# Schematic_1.net
KiCad netlist of a schematic drawn in Altium Designer
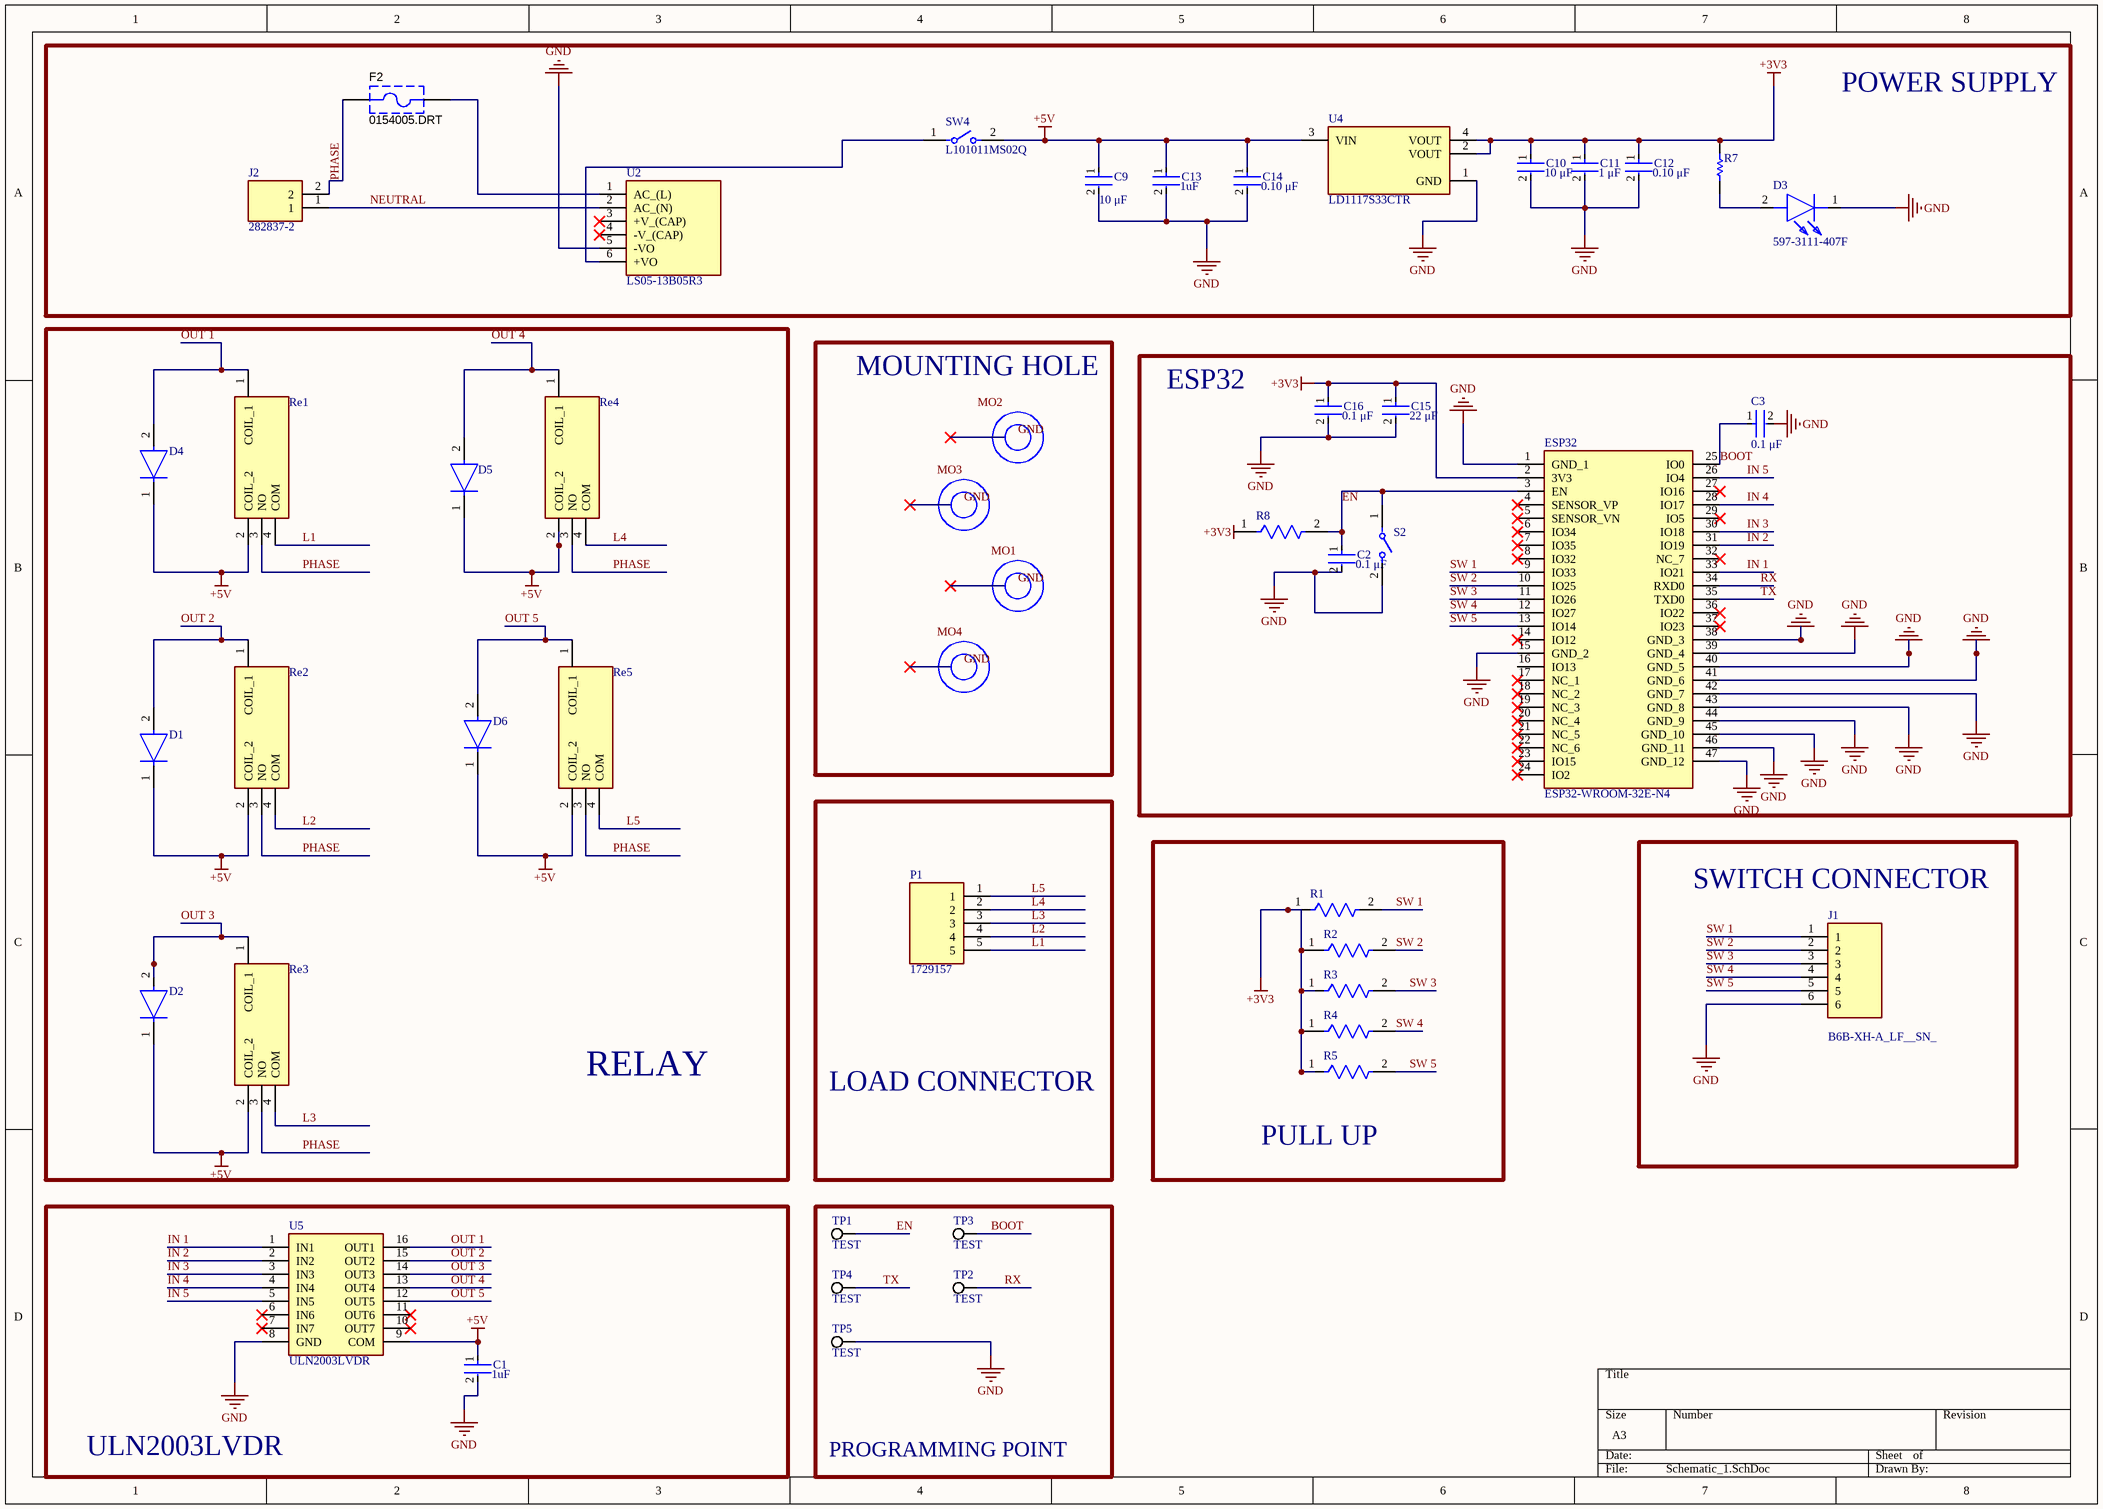
[diagram p0: Schematic_1.SchDoc]

(export (version "E")
  (design (tool "Eeschema 10.0.6"))
  (components
    (comp (ref "C1")
      (value "C0402C104K8PACTU")
      (footprint "FP-C0402-BB-MFG")
      (description "CAP CER 0.1UF 10V X5R 0402")
      (fields
        (field (name "CAPACITANCE") "1uF")
        (field (name "MANUFACTURER") "Kemet")
        (field (name "TOLERANCE") "0.1")
      )
      (libsource (lib "Altium Content Vault") (part "b4654b650e69147ec39a6b967a45e02"))
    )
    (comp (ref "C2")
      (value "0.1 μF")
      (footprint "FP-C0402-BB-MFG")
      (description "CAP CER 0.1UF 10V X5R 0402")
      (fields (field (name "MANUFACTURER") "Kemet") (field (name "TOLERANCE") "0.1"))
      (libsource (lib "Altium Content Vault") (part "b4654b650e69147ec39a6b967a45e02"))
    )
    (comp (ref "C3")
      (value "0.1 μF")
      (footprint "FP-C0402-BB-MFG")
      (description "CAP CER 0.1UF 10V X5R 0402")
      (fields (field (name "MANUFACTURER") "Kemet") (field (name "TOLERANCE") "0.1"))
      (libsource (lib "Altium Content Vault") (part "b4654b650e69147ec39a6b967a45e02"))
    )
    (comp (ref "C9")
      (value "10 μF")
      (footprint "FP-C0402-BB-MFG")
      (description "CAP CER 0.1UF 10V X5R 0402")
      (fields (field (name "MANUFACTURER") "Kemet") (field (name "TOLERANCE") "0.1"))
      (libsource (lib "Altium Content Vault") (part "b4654b650e69147ec39a6b967a45e02"))
    )
    (comp (ref "C10")
      (value "10 μF")
      (footprint "FP-C0402-BB-MFG")
      (description "CAP CER 0.1UF 10V X5R 0402")
      (fields (field (name "MANUFACTURER") "Kemet") (field (name "TOLERANCE") "0.1"))
      (libsource (lib "Altium Content Vault") (part "b4654b650e69147ec39a6b967a45e02"))
    )
    (comp (ref "C11")
      (value "1 μF")
      (footprint "FP-C0402-BB-MFG")
      (description "CAP CER 0.1UF 10V X5R 0402")
      (fields (field (name "MANUFACTURER") "Kemet") (field (name "TOLERANCE") "0.1"))
      (libsource (lib "Altium Content Vault") (part "b4654b650e69147ec39a6b967a45e02"))
    )
    (comp (ref "C12")
      (value "C0402C104K8PACTU")
      (footprint "FP-C0402-BB-MFG")
      (description "CAP CER 0.1UF 10V X5R 0402")
      (fields
        (field (name "CAPACITANCE") "0.10 μF")
        (field (name "MANUFACTURER") "Kemet")
        (field (name "TOLERANCE") "0.1")
      )
      (libsource (lib "Altium Content Vault") (part "b4654b650e69147ec39a6b967a45e02"))
    )
    (comp (ref "C13")
      (value "C0402C104K8PACTU")
      (footprint "FP-C0402-BB-MFG")
      (description "CAP CER 0.1UF 10V X5R 0402")
      (fields
        (field (name "CAPACITANCE") "1uF")
        (field (name "MANUFACTURER") "Kemet")
        (field (name "TOLERANCE") "0.1")
      )
      (libsource (lib "Altium Content Vault") (part "b4654b650e69147ec39a6b967a45e02"))
    )
    (comp (ref "C14")
      (value "0.10 μF")
      (footprint "FP-C0402-BB-MFG")
      (description "CAP CER 0.1UF 10V X5R 0402")
      (fields (field (name "MANUFACTURER") "Kemet") (field (name "TOLERANCE") "0.1"))
      (libsource (lib "Altium Content Vault") (part "b4654b650e69147ec39a6b967a45e02"))
    )
    (comp (ref "C15")
      (value "22 μF")
      (footprint "FP-C0402-BB-MFG")
      (description "CAP CER 0.1UF 10V X5R 0402")
      (fields (field (name "MANUFACTURER") "Kemet") (field (name "TOLERANCE") "0.1"))
      (libsource (lib "Altium Content Vault") (part "b4654b650e69147ec39a6b967a45e02"))
    )
    (comp (ref "C16")
      (value "0.1 μF")
      (footprint "FP-C0402-BB-MFG")
      (description "CAP CER 0.1UF 10V X5R 0402")
      (fields (field (name "MANUFACTURER") "Kemet") (field (name "TOLERANCE") "0.1"))
      (libsource (lib "Altium Content Vault") (part "b4654b650e69147ec39a6b967a45e02"))
    )
    (comp (ref "D1")
      (value "1N4148")
      (footprint "FP-017AG-MFG")
      (description "DIODE GEN PURP 100V 200MA DO35")
      (fields (field (name "VOLTAGE") "100V"))
      (libsource (lib "Altium Content Vault") (part "d7152d700b627762746794eb795d46e"))
    )
    (comp (ref "D2")
      (value "1N4148")
      (footprint "FP-017AG-MFG")
      (description "DIODE GEN PURP 100V 200MA DO35")
      (fields (field (name "VOLTAGE") "100V"))
      (libsource (lib "Altium Content Vault") (part "d7152d700b627762746794eb795d46e"))
    )
    (comp (ref "D3")
      (value "597-3111-407F")
      (footprint "SamacSys:LEDC3015X150N")
      (description "LED")
      (fields (field (name "MOUSER PART NUMBER") "645-597-3111-407F"))
      (libsource (lib "*") (part "597-3111-407F"))
    )
    (comp (ref "D4")
      (value "1N4148")
      (footprint "FP-017AG-MFG")
      (description "DIODE GEN PURP 100V 200MA DO35")
      (fields (field (name "VOLTAGE") "100V"))
      (libsource (lib "Altium Content Vault") (part "d7152d700b627762746794eb795d46e"))
    )
    (comp (ref "D5")
      (value "1N4148")
      (footprint "FP-017AG-MFG")
      (description "DIODE GEN PURP 100V 200MA DO35")
      (fields (field (name "VOLTAGE") "100V"))
      (libsource (lib "Altium Content Vault") (part "d7152d700b627762746794eb795d46e"))
    )
    (comp (ref "D6")
      (value "1N4148")
      (footprint "FP-017AG-MFG")
      (description "DIODE GEN PURP 100V 200MA DO35")
      (fields (field (name "VOLTAGE") "100V"))
      (libsource (lib "Altium Content Vault") (part "d7152d700b627762746794eb795d46e"))
    )
    (comp (ref "ESP32")
      (value "ESP32-WROOM-32E-N4")
      (footprint "SamacSys:ESP32WROOM32EN4")
      (description "Integrated Circuit")
      (fields (field (name "MOUSER PART NUMBER") "356-ESP32WRM32E132PH"))
      (libsource (lib "*") (part "ESP32-WROOM-32E-N4"))
    )
    (comp (ref "F2")
      (value "0154005.DRT")
      (footprint "LFUS-154_V")
      (description "Fuse and Holder Combination, 125 V, 5 A, -55 to 125 degC, 2-Pin SMD, RoHS, Tape and Reel")
      (fields (field (name "MANUFACTURER") "Littelfuse"))
      (libsource (lib "Altium Content Vault") (part "FUSE_HOLDER-2"))
    )
    (comp (ref "J1")
      (value "B6B-XH-A_LF__SN_")
      (footprint "SamacSys:SHDR6W64P0X250_1X6_1740X575X700P")
      (description "Connector")
      (fields
        (field (name "MANUFACTURER_PART_NUMBER") "B6B-XH-A(LF)(SN)")
        (field (name "MOUSER PART NUMBER") "306-B6BXHALFSN")
      )
      (libsource (lib "*") (part "B6B-XH-A_LF__SN_"))
    )
    (comp (ref "J2")
      (value "282837-2")
      (footprint "SamacSys:2828372")
      (description "Connector")
      (fields (field (name "MOUSER PART NUMBER") "571-2828372"))
      (libsource (lib "*") (part "282837-2"))
    )
    (comp (ref "P1")
      (value "1729157")
      (footprint "SamacSys:1729157")
      (description "Connector")
      (fields (field (name "MOUSER PART NUMBER") "651-1729157"))
      (libsource (lib "*") (part "1729157"))
    )
    (comp (ref "R1")
      (value "CRCW040210K0JNED")
      (footprint "FP-CRCW0402-e3-IPC_B")
      (description "RES Thick Film, 10kΩ, 5%, 0.063W, 200ppm/°C, 0402")
      (fields (field (name "TOLERANCE") "5%"))
      (libsource (lib "Altium Content Vault") (part "1029c3af85768c4190bb7ad29bc67b5"))
    )
    (comp (ref "R2")
      (value "CRCW040210K0JNED")
      (footprint "FP-CRCW0402-e3-IPC_B")
      (description "RES Thick Film, 10kΩ, 5%, 0.063W, 200ppm/°C, 0402")
      (fields (field (name "TOLERANCE") "5%"))
      (libsource (lib "Altium Content Vault") (part "1029c3af85768c4190bb7ad29bc67b5"))
    )
    (comp (ref "R3")
      (value "CRCW040210K0JNED")
      (footprint "FP-CRCW0402-e3-IPC_B")
      (description "RES Thick Film, 10kΩ, 5%, 0.063W, 200ppm/°C, 0402")
      (fields (field (name "TOLERANCE") "5%"))
      (libsource (lib "Altium Content Vault") (part "1029c3af85768c4190bb7ad29bc67b5"))
    )
    (comp (ref "R4")
      (value "CRCW040210K0JNED")
      (footprint "FP-CRCW0402-e3-IPC_B")
      (description "RES Thick Film, 10kΩ, 5%, 0.063W, 200ppm/°C, 0402")
      (fields (field (name "TOLERANCE") "5%"))
      (libsource (lib "Altium Content Vault") (part "1029c3af85768c4190bb7ad29bc67b5"))
    )
    (comp (ref "R5")
      (value "CRCW040210K0JNED")
      (footprint "FP-CRCW0402-e3-IPC_B")
      (description "RES Thick Film, 10kΩ, 5%, 0.063W, 200ppm/°C, 0402")
      (fields (field (name "TOLERANCE") "5%"))
      (libsource (lib "Altium Content Vault") (part "1029c3af85768c4190bb7ad29bc67b5"))
    )
    (comp (ref "R7")
      (value "ERJ-3EKF3300V")
      (footprint "RESC1608X55X30LL15T15")
      (description "Chip Resistor, 330 Ohm, +/- 1%, 0.1 W, -55 to 155 degC, 0603 (1608 Metric), RoHS, Tape and Reel")
      (libsource (lib "Altium Content Vault") (part "RES-2"))
    )
    (comp (ref "R8")
      (value "CRCW040210K0JNED")
      (footprint "FP-CRCW0402-e3-IPC_B")
      (description "RES Thick Film, 10kΩ, 5%, 0.063W, 200ppm/°C, 0402")
      (fields (field (name "TOLERANCE") "5%"))
      (libsource (lib "Altium Content Vault") (part "1029c3af85768c4190bb7ad29bc67b5"))
    )
    (comp (ref "Re1")
      (value "HF46F-G_5-HS1T")
      (footprint "SamacSys:HF46FG5HS1T")
      (description "Relay or Contactor")
      (fields (field (name "MANUFACTURER_PART_NUMBER") "HF46F-G/5-HS1T"))
      (libsource (lib "*") (part "HF46F-G_5-HS1T"))
    )
    (comp (ref "Re2")
      (value "HF46F-G_5-HS1T")
      (footprint "SamacSys:HF46FG5HS1T")
      (description "Relay or Contactor")
      (fields (field (name "MANUFACTURER_PART_NUMBER") "HF46F-G/5-HS1T"))
      (libsource (lib "*") (part "HF46F-G_5-HS1T"))
    )
    (comp (ref "Re3")
      (value "HF46F-G_5-HS1T")
      (footprint "SamacSys:HF46FG5HS1T")
      (description "Relay or Contactor")
      (fields (field (name "MANUFACTURER_PART_NUMBER") "HF46F-G/5-HS1T"))
      (libsource (lib "*") (part "HF46F-G_5-HS1T"))
    )
    (comp (ref "Re4")
      (value "HF46F-G_5-HS1T")
      (footprint "SamacSys:HF46FG5HS1T")
      (description "Relay or Contactor")
      (fields (field (name "MANUFACTURER_PART_NUMBER") "HF46F-G/5-HS1T"))
      (libsource (lib "*") (part "HF46F-G_5-HS1T"))
    )
    (comp (ref "Re5")
      (value "HF46F-G_5-HS1T")
      (footprint "SamacSys:HF46FG5HS1T")
      (description "Relay or Contactor")
      (fields (field (name "MANUFACTURER_PART_NUMBER") "HF46F-G/5-HS1T"))
      (libsource (lib "*") (part "HF46F-G_5-HS1T"))
    )
    (comp (ref "S2")
      (value "L101011MS02Q")
      (footprint "FP-L101011MS02Q-MFG")
      (description "SWITCH SLIDE SPST 4A 125V")
      (libsource (lib "Altium Content Vault") (part "bb27bde45df87f1f469753f287ef5ae"))
    )
    (comp (ref "SW4")
      (value "L101011MS02Q")
      (footprint "FP-L101011MS02Q-MFG")
      (description "SWITCH SLIDE SPST 4A 125V")
      (libsource (lib "Altium Content Vault") (part "bb27bde45df87f1f469753f287ef5ae"))
    )
    (comp (ref "TP1")
      (value "TEST")
      (footprint "KSTN-5012_V")
      (description "Test Point, White, Through Hole, RoHS, Bulk")
      (fields (field (name "MANUFACTURER") "Keystone"))
      (libsource (lib "Altium Content Vault") (part "TESTPOINT_WHITE"))
    )
    (comp (ref "TP2")
      (value "TEST")
      (footprint "KSTN-5012_V")
      (description "Test Point, White, Through Hole, RoHS, Bulk")
      (fields (field (name "MANUFACTURER") "Keystone"))
      (libsource (lib "Altium Content Vault") (part "TESTPOINT_WHITE"))
    )
    (comp (ref "TP3")
      (value "TEST")
      (footprint "KSTN-5012_V")
      (description "Test Point, White, Through Hole, RoHS, Bulk")
      (fields (field (name "MANUFACTURER") "Keystone"))
      (libsource (lib "Altium Content Vault") (part "TESTPOINT_WHITE"))
    )
    (comp (ref "TP4")
      (value "TEST")
      (footprint "KSTN-5012_V")
      (description "Test Point, White, Through Hole, RoHS, Bulk")
      (fields (field (name "MANUFACTURER") "Keystone"))
      (libsource (lib "Altium Content Vault") (part "TESTPOINT_WHITE"))
    )
    (comp (ref "TP5")
      (value "TEST")
      (footprint "KSTN-5012_V")
      (description "Test Point, White, Through Hole, RoHS, Bulk")
      (fields (field (name "MANUFACTURER") "Keystone"))
      (libsource (lib "Altium Content Vault") (part "TESTPOINT_WHITE"))
    )
    (comp (ref "U2")
      (value "LS05-13B05R3")
      (footprint "SamacSys:LS0513B05R3")
      (description "Power Supply")
      (libsource (lib "*") (part "LS05-13B05R3"))
    )
    (comp (ref "U4")
      (value "LD1117S33CTR")
      (footprint "FP-SOT-223-0046067_14-MFG")
      (description "IC REG LINEAR 3.3V 800MA SOT223")
      (libsource (lib "Altium Content Vault") (part "7818869c5c16ceab15634627166a29d"))
    )
    (comp (ref "U5")
      (value "ULN2003LVDR")
      (footprint "SamacSys:SOIC127P600X175-16N")
      (description "Integrated Circuit")
      (fields (field (name "MOUSER PART NUMBER") "595-ULN2003LVDR"))
      (libsource (lib "*") (part "ULN2003LVDR"))
    )
  )
  (nets
    (net (code "1") (name "+3V3") (class "Default")
      (node (ref "C10") (pin "1") (pinfunction "1_1") (pintype "passive"))
      (node (ref "C11") (pin "1") (pinfunction "1_1") (pintype "passive"))
      (node (ref "C12") (pin "1") (pinfunction "1_1") (pintype "passive"))
      (node (ref "C15") (pin "1") (pinfunction "1_1") (pintype "passive"))
      (node (ref "C16") (pin "1") (pinfunction "1_1") (pintype "passive"))
      (node (ref "ESP32") (pin "2") (pinfunction "3V3_2") (pintype "passive"))
      (node (ref "R1") (pin "1") (pinfunction "1_1") (pintype "passive"))
      (node (ref "R2") (pin "1") (pinfunction "1_1") (pintype "passive"))
      (node (ref "R3") (pin "1") (pinfunction "1_1") (pintype "passive"))
      (node (ref "R4") (pin "1") (pinfunction "1_1") (pintype "passive"))
      (node (ref "R5") (pin "1") (pinfunction "1_1") (pintype "passive"))
      (node (ref "R7") (pin "2") (pinfunction "2_2") (pintype "passive"))
      (node (ref "U4") (pin "2") (pinfunction "VOUT_2") (pintype "power_in"))
      (node (ref "U4") (pin "4") (pinfunction "VOUT_4") (pintype "power_in"))
    )
    (net (code "2") (name "+5V") (class "Default")
      (node (ref "C1") (pin "1") (pinfunction "1_1") (pintype "passive"))
      (node (ref "C13") (pin "1") (pinfunction "1_1") (pintype "passive"))
      (node (ref "C14") (pin "1") (pinfunction "1_1") (pintype "passive"))
      (node (ref "C9") (pin "1") (pinfunction "1_1") (pintype "passive"))
      (node (ref "D1") (pin "1") (pinfunction "C_1") (pintype "passive"))
      (node (ref "D2") (pin "1") (pinfunction "C_1") (pintype "passive"))
      (node (ref "D4") (pin "1") (pinfunction "C_1") (pintype "passive"))
      (node (ref "D5") (pin "1") (pinfunction "C_1") (pintype "passive"))
      (node (ref "D6") (pin "1") (pinfunction "C_1") (pintype "passive"))
      (node (ref "Re1") (pin "2") (pinfunction "COIL_2_2") (pintype "passive"))
      (node (ref "Re2") (pin "2") (pinfunction "COIL_2_2") (pintype "passive"))
      (node (ref "Re3") (pin "2") (pinfunction "COIL_2_2") (pintype "passive"))
      (node (ref "Re4") (pin "2") (pinfunction "COIL_2_2") (pintype "passive"))
      (node (ref "Re5") (pin "2") (pinfunction "COIL_2_2") (pintype "passive"))
      (node (ref "SW4") (pin "2") (pinfunction "2_2") (pintype "passive"))
      (node (ref "U4") (pin "3") (pinfunction "VIN_3") (pintype "power_in"))
      (node (ref "U5") (pin "9") (pinfunction "COM_9") (pintype "passive"))
    )
    (net (code "3") (name "/BOOT") (class "Default")
      (node (ref "C3") (pin "1") (pinfunction "1_1") (pintype "passive"))
      (node (ref "ESP32") (pin "25") (pinfunction "IO0_25") (pintype "passive"))
      (node (ref "TP3") (pin "1") (pinfunction "1_1") (pintype "passive"))
    )
    (net (code "4") (name "/EN") (class "Default")
      (node (ref "C2") (pin "1") (pinfunction "1_1") (pintype "passive"))
      (node (ref "ESP32") (pin "3") (pinfunction "EN_3") (pintype "passive"))
      (node (ref "R8") (pin "2") (pinfunction "2_2") (pintype "passive"))
      (node (ref "S2") (pin "1") (pinfunction "1_1") (pintype "passive"))
      (node (ref "TP1") (pin "1") (pinfunction "1_1") (pintype "passive"))
    )
    (net (code "5") (name "/IN 1") (class "Default")
      (node (ref "ESP32") (pin "33") (pinfunction "IO21_33") (pintype "passive"))
      (node (ref "U5") (pin "1") (pinfunction "IN1_1") (pintype "passive"))
    )
    (net (code "6") (name "/IN 2") (class "Default")
      (node (ref "ESP32") (pin "31") (pinfunction "IO19_31") (pintype "passive"))
      (node (ref "U5") (pin "2") (pinfunction "IN2_2") (pintype "passive"))
    )
    (net (code "7") (name "/IN 3") (class "Default")
      (node (ref "ESP32") (pin "30") (pinfunction "IO18_30") (pintype "passive"))
      (node (ref "U5") (pin "3") (pinfunction "IN3_3") (pintype "passive"))
    )
    (net (code "8") (name "/IN 4") (class "Default")
      (node (ref "ESP32") (pin "28") (pinfunction "IO17_28") (pintype "passive"))
      (node (ref "U5") (pin "4") (pinfunction "IN4_4") (pintype "passive"))
    )
    (net (code "9") (name "/IN 5") (class "Default")
      (node (ref "ESP32") (pin "26") (pinfunction "IO4_26") (pintype "passive"))
      (node (ref "U5") (pin "5") (pinfunction "IN5_5") (pintype "passive"))
    )
    (net (code "10") (name "/L1") (class "Default")
      (node (ref "P1") (pin "5") (pinfunction "5_5") (pintype "passive"))
      (node (ref "Re1") (pin "4") (pinfunction "COM_4") (pintype "passive"))
    )
    (net (code "11") (name "/L2") (class "Default")
      (node (ref "P1") (pin "4") (pinfunction "4_4") (pintype "passive"))
      (node (ref "Re2") (pin "4") (pinfunction "COM_4") (pintype "passive"))
    )
    (net (code "12") (name "/L3") (class "Default")
      (node (ref "P1") (pin "3") (pinfunction "3_3") (pintype "passive"))
      (node (ref "Re3") (pin "4") (pinfunction "COM_4") (pintype "passive"))
    )
    (net (code "13") (name "/L4") (class "Default")
      (node (ref "P1") (pin "2") (pinfunction "2_2") (pintype "passive"))
      (node (ref "Re4") (pin "4") (pinfunction "COM_4") (pintype "passive"))
    )
    (net (code "14") (name "/L5") (class "Default")
      (node (ref "P1") (pin "1") (pinfunction "1_1") (pintype "passive"))
      (node (ref "Re5") (pin "4") (pinfunction "COM_4") (pintype "passive"))
    )
    (net (code "19") (name "/NEUTRAL") (class "Default")
      (node (ref "J2") (pin "1") (pinfunction "1_1") (pintype "passive"))
      (node (ref "U2") (pin "2") (pinfunction "AC_(N)_2") (pintype "passive"))
    )
    (net (code "20") (name "/OUT 1") (class "Default")
      (node (ref "D4") (pin "2") (pinfunction "A_2") (pintype "passive"))
      (node (ref "Re1") (pin "1") (pinfunction "COIL_1_1") (pintype "passive"))
      (node (ref "U5") (pin "16") (pinfunction "OUT1_16") (pintype "passive"))
    )
    (net (code "21") (name "/OUT 2") (class "Default")
      (node (ref "D1") (pin "2") (pinfunction "A_2") (pintype "passive"))
      (node (ref "Re2") (pin "1") (pinfunction "COIL_1_1") (pintype "passive"))
      (node (ref "U5") (pin "15") (pinfunction "OUT2_15") (pintype "passive"))
    )
    (net (code "22") (name "/OUT 3") (class "Default")
      (node (ref "D2") (pin "2") (pinfunction "A_2") (pintype "passive"))
      (node (ref "Re3") (pin "1") (pinfunction "COIL_1_1") (pintype "passive"))
      (node (ref "U5") (pin "14") (pinfunction "OUT3_14") (pintype "passive"))
    )
    (net (code "23") (name "/OUT 4") (class "Default")
      (node (ref "D5") (pin "2") (pinfunction "A_2") (pintype "passive"))
      (node (ref "Re4") (pin "1") (pinfunction "COIL_1_1") (pintype "passive"))
      (node (ref "U5") (pin "13") (pinfunction "OUT4_13") (pintype "passive"))
    )
    (net (code "24") (name "/OUT 5") (class "Default")
      (node (ref "D6") (pin "2") (pinfunction "A_2") (pintype "passive"))
      (node (ref "Re5") (pin "1") (pinfunction "COIL_1_1") (pintype "passive"))
      (node (ref "U5") (pin "12") (pinfunction "OUT5_12") (pintype "passive"))
    )
    (net (code "25") (name "/PHASE") (class "Default")
      (node (ref "F2") (pin "1") (pinfunction "1_1") (pintype "passive"))
      (node (ref "J2") (pin "2") (pinfunction "2_2") (pintype "passive"))
      (node (ref "Re1") (pin "3") (pinfunction "NO_3") (pintype "passive"))
      (node (ref "Re2") (pin "3") (pinfunction "NO_3") (pintype "passive"))
      (node (ref "Re3") (pin "3") (pinfunction "NO_3") (pintype "passive"))
      (node (ref "Re4") (pin "3") (pinfunction "NO_3") (pintype "passive"))
      (node (ref "Re5") (pin "3") (pinfunction "NO_3") (pintype "passive"))
    )
    (net (code "26") (name "/RX") (class "Default")
      (node (ref "ESP32") (pin "34") (pinfunction "RXD0_34") (pintype "passive"))
      (node (ref "TP2") (pin "1") (pinfunction "1_1") (pintype "passive"))
    )
    (net (code "27") (name "/SW 1") (class "Default")
      (node (ref "ESP32") (pin "9") (pinfunction "IO33_9") (pintype "passive"))
      (node (ref "J1") (pin "1") (pinfunction "1_1") (pintype "passive"))
      (node (ref "R1") (pin "2") (pinfunction "2_2") (pintype "passive"))
    )
    (net (code "28") (name "/SW 2") (class "Default")
      (node (ref "ESP32") (pin "10") (pinfunction "IO25_10") (pintype "passive"))
      (node (ref "J1") (pin "2") (pinfunction "2_2") (pintype "passive"))
      (node (ref "R2") (pin "2") (pinfunction "2_2") (pintype "passive"))
    )
    (net (code "29") (name "/SW 3") (class "Default")
      (node (ref "ESP32") (pin "11") (pinfunction "IO26_11") (pintype "passive"))
      (node (ref "J1") (pin "3") (pinfunction "3_3") (pintype "passive"))
      (node (ref "R3") (pin "2") (pinfunction "2_2") (pintype "passive"))
    )
    (net (code "30") (name "/SW 4") (class "Default")
      (node (ref "ESP32") (pin "12") (pinfunction "IO27_12") (pintype "passive"))
      (node (ref "J1") (pin "4") (pinfunction "4_4") (pintype "passive"))
      (node (ref "R4") (pin "2") (pinfunction "2_2") (pintype "passive"))
    )
    (net (code "31") (name "/SW 5") (class "Default")
      (node (ref "ESP32") (pin "13") (pinfunction "IO14_13") (pintype "passive"))
      (node (ref "J1") (pin "5") (pinfunction "5_5") (pintype "passive"))
      (node (ref "R5") (pin "2") (pinfunction "2_2") (pintype "passive"))
    )
    (net (code "32") (name "/TX") (class "Default")
      (node (ref "ESP32") (pin "35") (pinfunction "TXD0_35") (pintype "passive"))
      (node (ref "TP4") (pin "1") (pinfunction "1_1") (pintype "passive"))
    )
    (net (code "33") (name "GND") (class "Default")
      (node (ref "C1") (pin "2") (pinfunction "2_2") (pintype "passive"))
      (node (ref "C10") (pin "2") (pinfunction "2_2") (pintype "passive"))
      (node (ref "C11") (pin "2") (pinfunction "2_2") (pintype "passive"))
      (node (ref "C12") (pin "2") (pinfunction "2_2") (pintype "passive"))
      (node (ref "C13") (pin "2") (pinfunction "2_2") (pintype "passive"))
      (node (ref "C14") (pin "2") (pinfunction "2_2") (pintype "passive"))
      (node (ref "C15") (pin "2") (pinfunction "2_2") (pintype "passive"))
      (node (ref "C16") (pin "2") (pinfunction "2_2") (pintype "passive"))
      (node (ref "C2") (pin "2") (pinfunction "2_2") (pintype "passive"))
      (node (ref "C3") (pin "2") (pinfunction "2_2") (pintype "passive"))
      (node (ref "C9") (pin "2") (pinfunction "2_2") (pintype "passive"))
      (node (ref "D3") (pin "1") (pinfunction "K_1") (pintype "passive"))
      (node (ref "ESP32") (pin "1") (pinfunction "GND_1_1") (pintype "passive"))
      (node (ref "ESP32") (pin "15") (pinfunction "GND_2_15") (pintype "passive"))
      (node (ref "ESP32") (pin "38") (pinfunction "GND_3_38") (pintype "passive"))
      (node (ref "ESP32") (pin "39") (pinfunction "GND_4_39") (pintype "passive"))
      (node (ref "ESP32") (pin "40") (pinfunction "GND_5_40") (pintype "passive"))
      (node (ref "ESP32") (pin "41") (pinfunction "GND_6_41") (pintype "passive"))
      (node (ref "ESP32") (pin "42") (pinfunction "GND_7_42") (pintype "passive"))
      (node (ref "ESP32") (pin "43") (pinfunction "GND_8_43") (pintype "passive"))
      (node (ref "ESP32") (pin "44") (pinfunction "GND_9_44") (pintype "passive"))
      (node (ref "ESP32") (pin "45") (pinfunction "GND_10_45") (pintype "passive"))
      (node (ref "ESP32") (pin "46") (pinfunction "GND_11_46") (pintype "passive"))
      (node (ref "ESP32") (pin "47") (pinfunction "GND_12_47") (pintype "passive"))
      (node (ref "J1") (pin "6") (pinfunction "6_6") (pintype "passive"))
      (node (ref "S2") (pin "2") (pinfunction "2_2") (pintype "passive"))
      (node (ref "TP5") (pin "1") (pinfunction "1_1") (pintype "passive"))
      (node (ref "U2") (pin "5") (pinfunction "-VO_5") (pintype "passive"))
      (node (ref "U4") (pin "1") (pinfunction "GND_1") (pintype "power_in"))
      (node (ref "U5") (pin "8") (pinfunction "GND_8") (pintype "passive"))
    )
    (net (code "34") (name "Net-(D3-A)") (class "Default")
      (node (ref "D3") (pin "2") (pinfunction "A_2") (pintype "passive"))
      (node (ref "R7") (pin "1") (pinfunction "1_1") (pintype "passive"))
    )
    (net (code "35") (name "Net-(U2-+VO)") (class "Default")
      (node (ref "SW4") (pin "1") (pinfunction "1_1") (pintype "passive"))
      (node (ref "U2") (pin "6") (pinfunction "+VO_6") (pintype "passive"))
    )
    (net (code "36") (name "Net-(U2-AC_(L))") (class "Default")
      (node (ref "F2") (pin "2") (pinfunction "2_2") (pintype "passive"))
      (node (ref "U2") (pin "1") (pinfunction "AC_(L)_1") (pintype "passive"))
    )
    (net (code "37") (name "unconnected-(ESP32-IO2-Pad24)") (class "Default")
      (node (ref "ESP32") (pin "24") (pinfunction "IO2_24") (pintype "passive+no_connect"))
    )
    (net (code "38") (name "unconnected-(ESP32-IO5-Pad29)") (class "Default")
      (node (ref "ESP32") (pin "29") (pinfunction "IO5_29") (pintype "passive+no_connect"))
    )
    (net (code "39") (name "unconnected-(ESP32-IO12-Pad14)") (class "Default")
      (node (ref "ESP32") (pin "14") (pinfunction "IO12_14") (pintype "passive+no_connect"))
    )
    (net (code "40") (name "unconnected-(ESP32-IO13-Pad16)") (class "Default")
      (node (ref "ESP32") (pin "16") (pinfunction "IO13_16") (pintype "passive"))
    )
    (net (code "41") (name "unconnected-(ESP32-IO15-Pad23)") (class "Default")
      (node (ref "ESP32") (pin "23") (pinfunction "IO15_23") (pintype "passive+no_connect"))
    )
    (net (code "42") (name "unconnected-(ESP32-IO16-Pad27)") (class "Default")
      (node (ref "ESP32") (pin "27") (pinfunction "IO16_27") (pintype "passive+no_connect"))
    )
    (net (code "43") (name "unconnected-(ESP32-IO22-Pad36)") (class "Default")
      (node (ref "ESP32") (pin "36") (pinfunction "IO22_36") (pintype "passive+no_connect"))
    )
    (net (code "44") (name "unconnected-(ESP32-IO23-Pad37)") (class "Default")
      (node (ref "ESP32") (pin "37") (pinfunction "IO23_37") (pintype "passive+no_connect"))
    )
    (net (code "45") (name "unconnected-(ESP32-IO32-Pad8)") (class "Default")
      (node (ref "ESP32") (pin "8") (pinfunction "IO32_8") (pintype "passive+no_connect"))
    )
    (net (code "46") (name "unconnected-(ESP32-IO34-Pad6)") (class "Default")
      (node (ref "ESP32") (pin "6") (pinfunction "IO34_6") (pintype "passive+no_connect"))
    )
    (net (code "47") (name "unconnected-(ESP32-IO35-Pad7)") (class "Default")
      (node (ref "ESP32") (pin "7") (pinfunction "IO35_7") (pintype "passive+no_connect"))
    )
    (net (code "48") (name "unconnected-(ESP32-NC_1-Pad17)") (class "Default")
      (node (ref "ESP32") (pin "17") (pinfunction "NC_1_17") (pintype "passive+no_connect"))
    )
    (net (code "49") (name "unconnected-(ESP32-NC_2-Pad18)") (class "Default")
      (node (ref "ESP32") (pin "18") (pinfunction "NC_2_18") (pintype "passive+no_connect"))
    )
    (net (code "50") (name "unconnected-(ESP32-NC_3-Pad19)") (class "Default")
      (node (ref "ESP32") (pin "19") (pinfunction "NC_3_19") (pintype "passive+no_connect"))
    )
    (net (code "51") (name "unconnected-(ESP32-NC_4-Pad20)") (class "Default")
      (node (ref "ESP32") (pin "20") (pinfunction "NC_4_20") (pintype "passive+no_connect"))
    )
    (net (code "52") (name "unconnected-(ESP32-NC_5-Pad21)") (class "Default")
      (node (ref "ESP32") (pin "21") (pinfunction "NC_5_21") (pintype "passive+no_connect"))
    )
    (net (code "53") (name "unconnected-(ESP32-NC_6-Pad22)") (class "Default")
      (node (ref "ESP32") (pin "22") (pinfunction "NC_6_22") (pintype "passive+no_connect"))
    )
    (net (code "54") (name "unconnected-(ESP32-NC_7-Pad32)") (class "Default")
      (node (ref "ESP32") (pin "32") (pinfunction "NC_7_32") (pintype "passive+no_connect"))
    )
    (net (code "55") (name "unconnected-(ESP32-SENSOR_VN-Pad5)") (class "Default")
      (node (ref "ESP32") (pin "5") (pinfunction "SENSOR_VN_5") (pintype "passive+no_connect"))
    )
    (net (code "56") (name "unconnected-(ESP32-SENSOR_VP-Pad4)") (class "Default")
      (node (ref "ESP32") (pin "4") (pinfunction "SENSOR_VP_4") (pintype "passive+no_connect"))
    )
    (net (code "57") (name "unconnected-(R8-Pad1)") (class "Default")
      (node (ref "R8") (pin "1") (pinfunction "1_1") (pintype "passive"))
    )
    (net (code "58") (name "unconnected-(U2-+V_(CAP)-Pad3)") (class "Default")
      (node (ref "U2") (pin "3") (pinfunction "+V_(CAP)_3") (pintype "passive+no_connect"))
    )
    (net (code "59") (name "unconnected-(U2--V_(CAP)-Pad4)") (class "Default")
      (node (ref "U2") (pin "4") (pinfunction "-V_(CAP)_4") (pintype "passive+no_connect"))
    )
    (net (code "60") (name "unconnected-(U5-IN6-Pad6)") (class "Default")
      (node (ref "U5") (pin "6") (pinfunction "IN6_6") (pintype "passive+no_connect"))
    )
    (net (code "61") (name "unconnected-(U5-IN7-Pad7)") (class "Default")
      (node (ref "U5") (pin "7") (pinfunction "IN7_7") (pintype "passive+no_connect"))
    )
    (net (code "62") (name "unconnected-(U5-OUT6-Pad11)") (class "Default")
      (node (ref "U5") (pin "11") (pinfunction "OUT6_11") (pintype "passive+no_connect"))
    )
    (net (code "63") (name "unconnected-(U5-OUT7-Pad10)") (class "Default")
      (node (ref "U5") (pin "10") (pinfunction "OUT7_10") (pintype "passive+no_connect"))
    )
  )
)
